# Carte_power.net
KiCad netlist of a schematic drawn in EAGLE
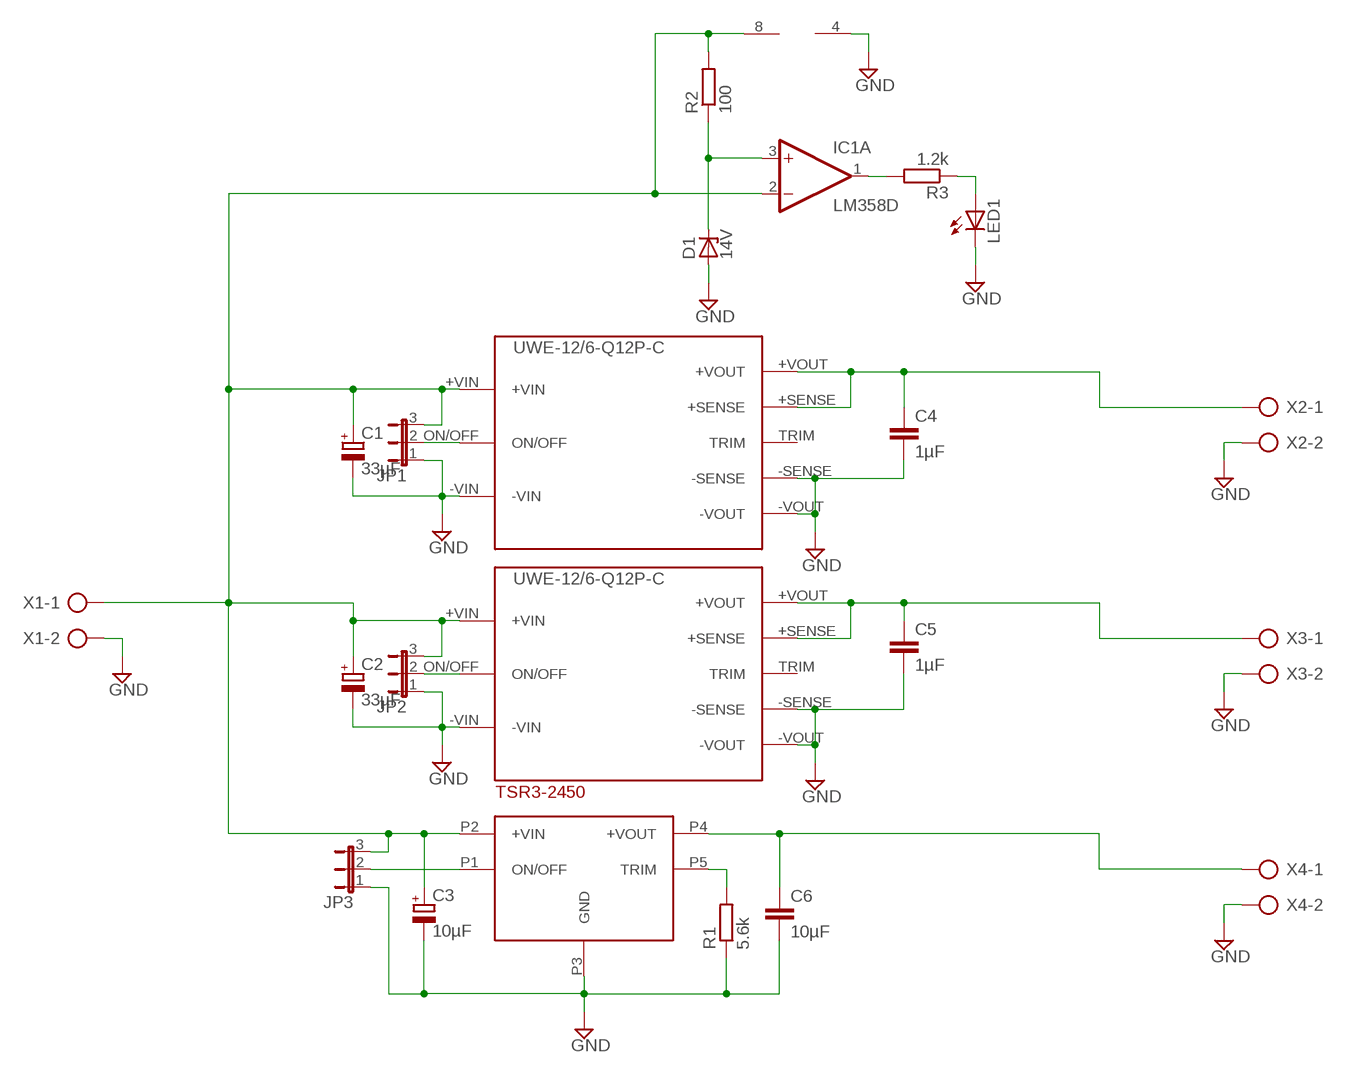
[diagram p0: schematic, sheet 1]

(export (version "E")
  (design (tool "Eeschema 10.0.6"))
  (components
    (comp (ref "C1")
      (value "33µF")
      (footprint "eagle-import:153CLV-1010")
      (libsource (lib "eagle-import") (part "CPOL-EU153CLV-1010"))
    )
    (comp (ref "C2")
      (value "33µF")
      (footprint "eagle-import:153CLV-1010")
      (libsource (lib "eagle-import") (part "CPOL-EU153CLV-1010"))
    )
    (comp (ref "C3")
      (value "10µF")
      (footprint "eagle-import:153CLV-1010")
      (libsource (lib "eagle-import") (part "CPOL-EU153CLV-1010"))
    )
    (comp (ref "C4")
      (value "1µF")
      (footprint "eagle-import:C2012")
      (libsource (lib "eagle-import") (part "C-EUC2012"))
    )
    (comp (ref "C5")
      (value "1µF")
      (footprint "eagle-import:C2012")
      (libsource (lib "eagle-import") (part "C-EUC2012"))
    )
    (comp (ref "C6")
      (value "10µF")
      (footprint "eagle-import:C2012")
      (libsource (lib "eagle-import") (part "C-EUC2012"))
    )
    (comp (ref "D1")
      (value "14V")
      (footprint "eagle-import:C1702-15")
      (libsource (lib "eagle-import") (part "1N5333"))
    )
    (comp (ref "IC1")
      (value "LM358D")
      (footprint "eagle-import:SO08")
      (libsource (lib "eagle-import") (part "LM358D"))
    )
    (comp (ref "JP1")
      (value "JP2E")
      (footprint "eagle-import:JP2")
      (libsource (lib "eagle-import") (part "JP2E"))
    )
    (comp (ref "JP2")
      (value "JP2E")
      (footprint "eagle-import:JP2")
      (libsource (lib "eagle-import") (part "JP2E"))
    )
    (comp (ref "JP3")
      (value "JP2E")
      (footprint "eagle-import:JP2")
      (libsource (lib "eagle-import") (part "JP2E"))
    )
    (comp (ref "LED1")
      (value "LED5MM")
      (footprint "eagle-import:LED5MM")
      (libsource (lib "eagle-import") (part "LED5MM"))
    )
    (comp (ref "R1")
      (value "5.6k")
      (footprint "eagle-import:R2012")
      (libsource (lib "eagle-import") (part "R-EU_R2012"))
    )
    (comp (ref "R2")
      (value "100")
      (footprint "eagle-import:R2012")
      (libsource (lib "eagle-import") (part "R-EU_R2012"))
    )
    (comp (ref "R3")
      (value "1.2k")
      (footprint "eagle-import:R2012")
      (libsource (lib "eagle-import") (part "R-EU_R2012"))
    )
    (comp (ref "U$1")
      (value "UWE-12/6-Q12P-C")
      (footprint "eagle-import:UWE-12_6-Q12P-C")
      (libsource (lib "eagle-import") (part "UWE-12/6-Q12P-C"))
    )
    (comp (ref "U$2")
      (value "TSR3-2450")
      (footprint "eagle-import:TSR3-2450")
      (libsource (lib "eagle-import") (part "TSR3-2450"))
    )
    (comp (ref "U$4")
      (value "UWE-12/6-Q12P-C")
      (footprint "eagle-import:UWE-12_6-Q12P-C")
      (libsource (lib "eagle-import") (part "UWE-12/6-Q12P-C"))
    )
    (comp (ref "X1")
      (value "AK300/2")
      (footprint "eagle-import:AK300_2")
      (libsource (lib "eagle-import") (part "AK300/2"))
    )
    (comp (ref "X2")
      (value "AK300/2")
      (footprint "eagle-import:AK300_2")
      (libsource (lib "eagle-import") (part "AK300/2"))
    )
    (comp (ref "X3")
      (value "AK300/2")
      (footprint "eagle-import:AK300_2")
      (libsource (lib "eagle-import") (part "AK300/2"))
    )
    (comp (ref "X4")
      (value "AK300/2")
      (footprint "eagle-import:AK300_2")
      (libsource (lib "eagle-import") (part "AK300/2"))
    )
  )
  (nets
    (net (code "1") (name "GND") (class "Default")
      (node (ref "C1") (pin "-") (pinfunction "-_-") (pintype "passive"))
      (node (ref "C2") (pin "-") (pinfunction "-_-") (pintype "passive"))
      (node (ref "C3") (pin "-") (pinfunction "-_-") (pintype "passive"))
      (node (ref "C4") (pin "2") (pinfunction "2_2") (pintype "passive"))
      (node (ref "C5") (pin "2") (pinfunction "2_2") (pintype "passive"))
      (node (ref "C6") (pin "2") (pinfunction "2_2") (pintype "passive"))
      (node (ref "D1") (pin "A") (pinfunction "A_A") (pintype "passive"))
      (node (ref "IC1") (pin "4") (pinfunction "V-_4") (pintype "power_in"))
      (node (ref "JP1") (pin "1") (pinfunction "1_1") (pintype "passive"))
      (node (ref "JP2") (pin "1") (pinfunction "1_1") (pintype "passive"))
      (node (ref "JP3") (pin "1") (pinfunction "1_1") (pintype "passive"))
      (node (ref "LED1") (pin "K") (pinfunction "C_K") (pintype "passive"))
      (node (ref "R1") (pin "1") (pinfunction "1_1") (pintype "passive"))
      (node (ref "U$1") (pin "-SENSE") (pinfunction "-SENSE_-SENSE") (pintype "input"))
      (node (ref "U$1") (pin "-VIN") (pinfunction "-VIN_-VIN") (pintype "input"))
      (node (ref "U$1") (pin "-VOUT") (pinfunction "-VOUT_-VOUT") (pintype "output"))
      (node (ref "U$2") (pin "P3") (pinfunction "GND_P3") (pintype "input"))
      (node (ref "U$4") (pin "-SENSE") (pinfunction "-SENSE_-SENSE") (pintype "input"))
      (node (ref "U$4") (pin "-VIN") (pinfunction "-VIN_-VIN") (pintype "input"))
      (node (ref "U$4") (pin "-VOUT") (pinfunction "-VOUT_-VOUT") (pintype "output"))
      (node (ref "X1") (pin "2") (pinfunction "KL_2") (pintype "passive"))
      (node (ref "X2") (pin "2") (pinfunction "KL_2") (pintype "passive"))
      (node (ref "X3") (pin "2") (pinfunction "KL_2") (pintype "passive"))
      (node (ref "X4") (pin "2") (pinfunction "KL_2") (pintype "passive"))
    )
    (net (code "2") (name "Net-(IC1A-+IN)") (class "Default")
      (node (ref "D1") (pin "C") (pinfunction "C_C") (pintype "passive"))
      (node (ref "IC1") (pin "3") (pinfunction "+IN_3") (pintype "input"))
      (node (ref "R2") (pin "1") (pinfunction "1_1") (pintype "passive"))
    )
    (net (code "3") (name "Net-(IC1A--IN)") (class "Default")
      (node (ref "C1") (pin "+") (pinfunction "+_+") (pintype "passive"))
      (node (ref "C2") (pin "+") (pinfunction "+_+") (pintype "passive"))
      (node (ref "C3") (pin "+") (pinfunction "+_+") (pintype "passive"))
      (node (ref "IC1") (pin "2") (pinfunction "-IN_2") (pintype "input"))
      (node (ref "IC1") (pin "8") (pinfunction "V+_8") (pintype "power_in"))
      (node (ref "JP1") (pin "3") (pinfunction "3_3") (pintype "passive"))
      (node (ref "JP2") (pin "3") (pinfunction "3_3") (pintype "passive"))
      (node (ref "JP3") (pin "3") (pinfunction "3_3") (pintype "passive"))
      (node (ref "R2") (pin "2") (pinfunction "2_2") (pintype "passive"))
      (node (ref "U$1") (pin "+VIN") (pinfunction "+VIN_+VIN") (pintype "input"))
      (node (ref "U$2") (pin "P2") (pinfunction "+VIN_P2") (pintype "input"))
      (node (ref "U$4") (pin "+VIN") (pinfunction "+VIN_+VIN") (pintype "input"))
      (node (ref "X1") (pin "1") (pinfunction "KL_1") (pintype "passive"))
    )
    (net (code "4") (name "Net-(IC1A-OUT)") (class "Default")
      (node (ref "IC1") (pin "1") (pinfunction "OUT_1") (pintype "output"))
      (node (ref "R3") (pin "2") (pinfunction "2_2") (pintype "passive"))
    )
    (net (code "5") (name "Net-(JP1-Pad2)") (class "Default")
      (node (ref "JP1") (pin "2") (pinfunction "2_2") (pintype "passive"))
      (node (ref "U$4") (pin "ON/OFF") (pinfunction "ON/OFF_ON/OFF") (pintype "input"))
    )
    (net (code "6") (name "Net-(JP2-Pad2)") (class "Default")
      (node (ref "JP2") (pin "2") (pinfunction "2_2") (pintype "passive"))
      (node (ref "U$1") (pin "ON/OFF") (pinfunction "ON/OFF_ON/OFF") (pintype "input"))
    )
    (net (code "7") (name "Net-(LED1-PadA)") (class "Default")
      (node (ref "LED1") (pin "A") (pinfunction "A_A") (pintype "passive"))
      (node (ref "R3") (pin "1") (pinfunction "1_1") (pintype "passive"))
    )
    (net (code "8") (name "Net-(U$2-+VOUT)") (class "Default")
      (node (ref "C6") (pin "1") (pinfunction "1_1") (pintype "passive"))
      (node (ref "U$2") (pin "P4") (pinfunction "+VOUT_P4") (pintype "output"))
      (node (ref "X4") (pin "1") (pinfunction "KL_1") (pintype "passive"))
    )
    (net (code "9") (name "Net-(U$2-ON{slash}OFF)") (class "Default")
      (node (ref "JP3") (pin "2") (pinfunction "2_2") (pintype "passive"))
      (node (ref "U$2") (pin "P1") (pinfunction "ON/OFF_P1") (pintype "input"))
    )
    (net (code "10") (name "Net-(U$2-TRIM)") (class "Default")
      (node (ref "R1") (pin "2") (pinfunction "2_2") (pintype "passive"))
      (node (ref "U$2") (pin "P5") (pinfunction "TRIM_P5") (pintype "input"))
    )
    (net (code "11") (name "Net-(X2A-KL)") (class "Default")
      (node (ref "C4") (pin "1") (pinfunction "1_1") (pintype "passive"))
      (node (ref "U$4") (pin "+SENSE") (pinfunction "+SENSE_+SENSE") (pintype "input"))
      (node (ref "U$4") (pin "+VOUT") (pinfunction "+VOUT_+VOUT") (pintype "output"))
      (node (ref "X2") (pin "1") (pinfunction "KL_1") (pintype "passive"))
    )
    (net (code "12") (name "Net-(X3A-KL)") (class "Default")
      (node (ref "C5") (pin "1") (pinfunction "1_1") (pintype "passive"))
      (node (ref "U$1") (pin "+SENSE") (pinfunction "+SENSE_+SENSE") (pintype "input"))
      (node (ref "U$1") (pin "+VOUT") (pinfunction "+VOUT_+VOUT") (pintype "output"))
      (node (ref "X3") (pin "1") (pinfunction "KL_1") (pintype "passive"))
    )
    (net (code "13") (name "unconnected-(U$1-PadTRIM)") (class "Default")
      (node (ref "U$1") (pin "TRIM") (pinfunction "TRIM_TRIM") (pintype "input"))
    )
    (net (code "14") (name "unconnected-(U$4-PadTRIM)") (class "Default")
      (node (ref "U$4") (pin "TRIM") (pinfunction "TRIM_TRIM") (pintype "input"))
    )
  )
)
